# Tiny_Tetris_v1_0.net
KiCad netlist of a schematic drawn in EAGLE
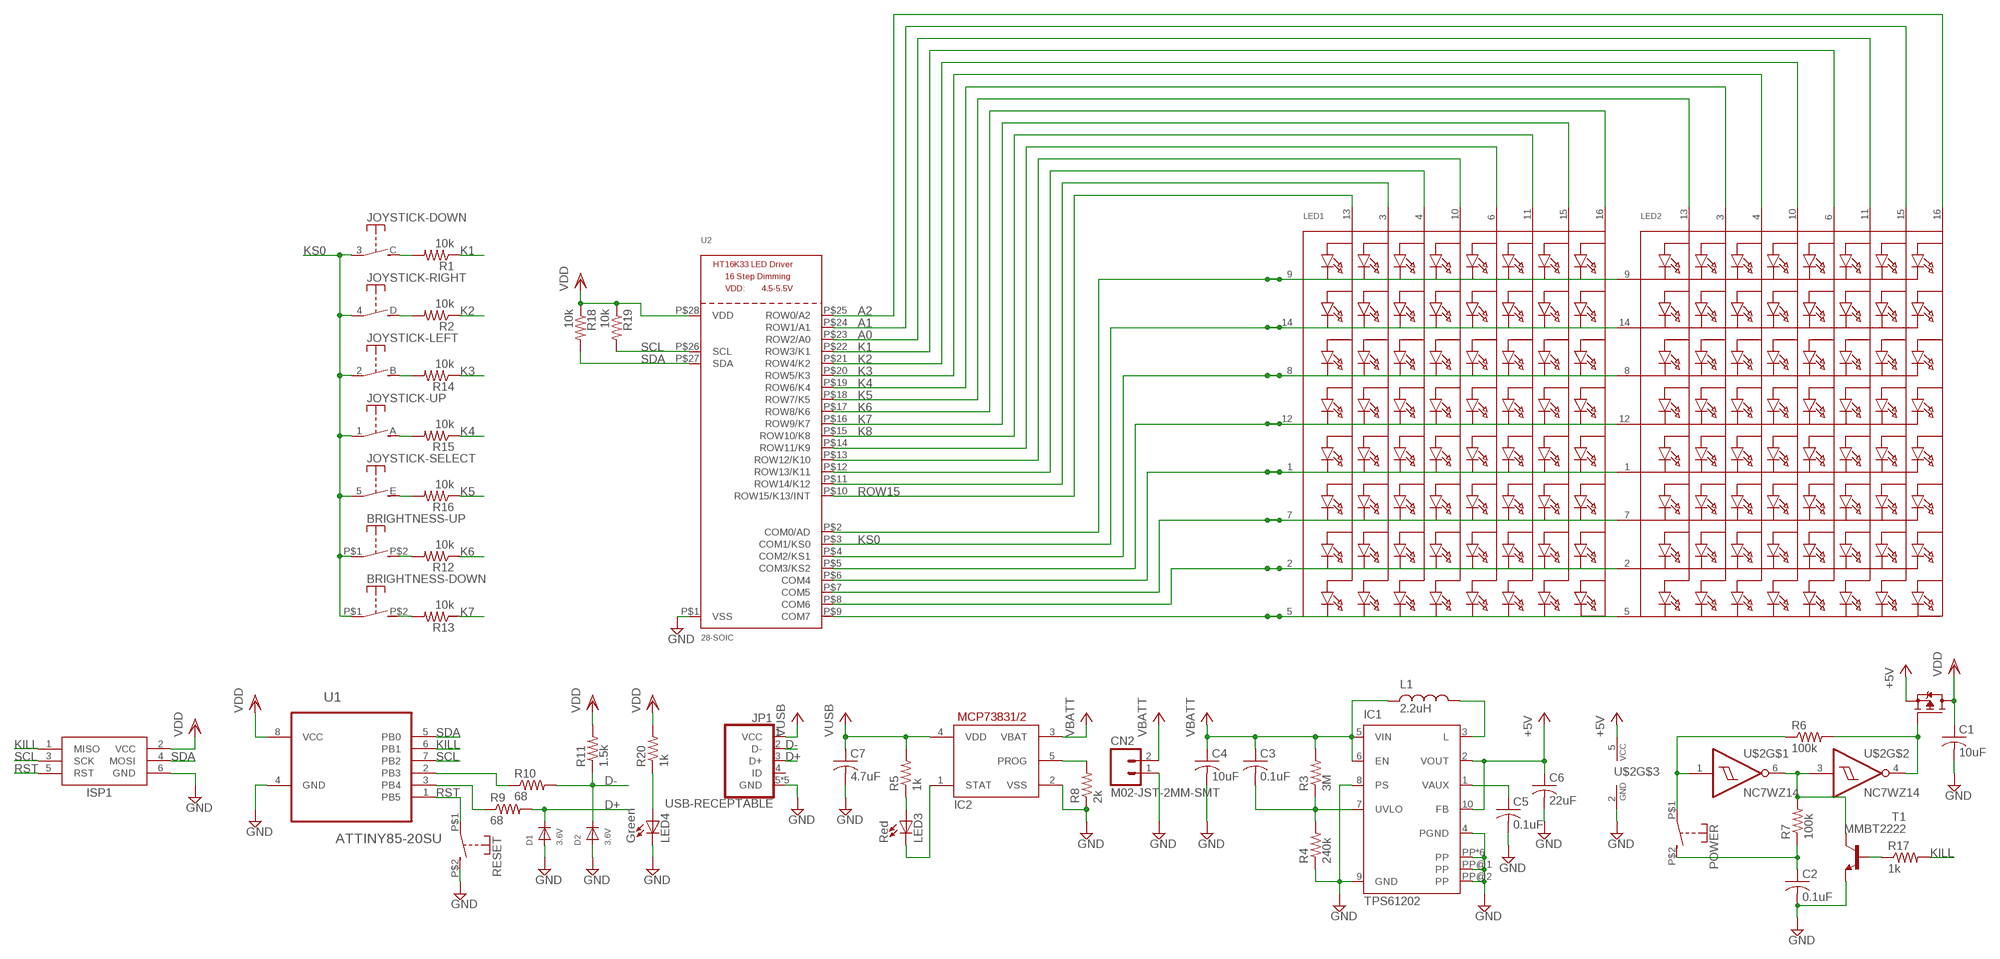
[diagram p0: schematic, sheet 1]

(export (version "E")
  (design (tool "Eeschema 10.0.6"))
  (components
    (comp (ref "BRIGHTNESS-DOWN")
      (value "SWITCH-TACTSKRELGE010")
      (footprint "eagle-import:TACT-ALPS-SKRELGE010")
      (libsource (lib "eagle-import") (part "SWITCH-TACTSKRELGE010"))
    )
    (comp (ref "BRIGHTNESS-UP")
      (value "SWITCH-TACTSKRELGE010")
      (footprint "eagle-import:TACT-ALPS-SKRELGE010")
      (libsource (lib "eagle-import") (part "SWITCH-TACTSKRELGE010"))
    )
    (comp (ref "C1")
      (value "10uF")
      (footprint "eagle-import:C0603K")
      (libsource (lib "eagle-import") (part "C-USC0603K"))
    )
    (comp (ref "C2")
      (value "0.1uF")
      (footprint "eagle-import:C0603K")
      (libsource (lib "eagle-import") (part "C-USC0603K"))
    )
    (comp (ref "C3")
      (value "0.1uF")
      (footprint "eagle-import:C0603K")
      (libsource (lib "eagle-import") (part "C-USC0603K"))
    )
    (comp (ref "C4")
      (value "10uF")
      (footprint "eagle-import:C0603K")
      (libsource (lib "eagle-import") (part "C-USC0603K"))
    )
    (comp (ref "C5")
      (value "0.1uF")
      (footprint "eagle-import:C0603K")
      (libsource (lib "eagle-import") (part "C-USC0603K"))
    )
    (comp (ref "C6")
      (value "22uF")
      (footprint "eagle-import:C0603K")
      (libsource (lib "eagle-import") (part "C-USC0603K"))
    )
    (comp (ref "C7")
      (value "4.7uF")
      (footprint "eagle-import:C0603K")
      (libsource (lib "eagle-import") (part "C-USC0603K"))
    )
    (comp (ref "CN2")
      (value "M02-JST-2MM-SMT")
      (footprint "eagle-import:1X02_NO_SILK")
      (libsource (lib "eagle-import") (part "M021X02_NO_SILK"))
    )
    (comp (ref "D1")
      (value "3.6V")
      (footprint "eagle-import:SOD-323")
      (libsource (lib "eagle-import") (part "DIODESOD-323"))
    )
    (comp (ref "D2")
      (value "3.6V")
      (footprint "eagle-import:SOD-323")
      (libsource (lib "eagle-import") (part "DIODESOD-323"))
    )
    (comp (ref "IC1")
      (value "TPS61202")
      (footprint "eagle-import:S-PDSO-N10")
      (fields (field (name "MPN") "TPS61202DRCR"))
      (libsource (lib "eagle-import") (part "TPS61202"))
    )
    (comp (ref "IC2")
      (value "MCP73831/OT")
      (footprint "eagle-import:SOT23-5L")
      (libsource (lib "eagle-import") (part "MCP73831/OT"))
    )
    (comp (ref "ISP1")
      (value "AVRISP-6")
      (footprint "eagle-import:AVRISP")
      (libsource (lib "eagle-import") (part "AVRISP-6"))
    )
    (comp (ref "JOYSTICK-")
      (value "SWITCH-NAVIGATION")
      (footprint "eagle-import:JOYSTICK-NOKIA-3230")
      (libsource (lib "eagle-import") (part "SWITCH-NAVIGATION"))
    )
    (comp (ref "JP1")
      (value "USB-RECEPTABLE")
      (footprint "eagle-import:FCI-10103594-0001LF")
      (libsource (lib "eagle-import") (part "USB-RECEPTABLE"))
    )
    (comp (ref "L1")
      (value "2.2uH")
      (footprint "eagle-import:LPS3015")
      (libsource (lib "eagle-import") (part "LPS3015"))
    )
    (comp (ref "LED1")
      (value "DISP_SEGMENT_8X8_ROWCATHODEBL-M12A883")
      (footprint "eagle-import:SEGMENT_BL-M12A883")
      (libsource (lib "eagle-import") (part "DISP_SEGMENT_8X8_ROWCATHODEBL-M12A883"))
    )
    (comp (ref "LED2")
      (value "DISP_SEGMENT_8X8_ROWCATHODEBL-M12A883")
      (footprint "eagle-import:SEGMENT_BL-M12A883")
      (libsource (lib "eagle-import") (part "DISP_SEGMENT_8X8_ROWCATHODEBL-M12A883"))
    )
    (comp (ref "LED3")
      (value "Red")
      (footprint "eagle-import:LED-0603-SIDEVIEW")
      (libsource (lib "eagle-import") (part "LED"))
    )
    (comp (ref "LED4")
      (value "Green")
      (footprint "eagle-import:LED-0603-SIDEVIEW")
      (libsource (lib "eagle-import") (part "LED"))
    )
    (comp (ref "POWER")
      (value "SWITCH-TACTSKRELGE010")
      (footprint "eagle-import:TACT-ALPS-SKRELGE010")
      (libsource (lib "eagle-import") (part "SWITCH-TACTSKRELGE010"))
    )
    (comp (ref "R1")
      (value "10k")
      (footprint "eagle-import:R0603")
      (libsource (lib "eagle-import") (part "R-US_R0603"))
    )
    (comp (ref "R2")
      (value "10k")
      (footprint "eagle-import:R0603")
      (libsource (lib "eagle-import") (part "R-US_R0603"))
    )
    (comp (ref "R3")
      (value "3M")
      (footprint "eagle-import:R0603")
      (libsource (lib "eagle-import") (part "R-US_R0603"))
    )
    (comp (ref "R4")
      (value "240k")
      (footprint "eagle-import:R0603")
      (libsource (lib "eagle-import") (part "R-US_R0603"))
    )
    (comp (ref "R5")
      (value "1k")
      (footprint "eagle-import:R0603")
      (libsource (lib "eagle-import") (part "R-US_R0603"))
    )
    (comp (ref "R6")
      (value "100k")
      (footprint "eagle-import:R0603")
      (libsource (lib "eagle-import") (part "R-US_R0603"))
    )
    (comp (ref "R7")
      (value "100k")
      (footprint "eagle-import:R0603")
      (libsource (lib "eagle-import") (part "R-US_R0603"))
    )
    (comp (ref "R8")
      (value "2k")
      (footprint "eagle-import:R0603")
      (libsource (lib "eagle-import") (part "R-US_R0603"))
    )
    (comp (ref "R9")
      (value "68")
      (footprint "eagle-import:R0603")
      (libsource (lib "eagle-import") (part "R-US_R0603"))
    )
    (comp (ref "R10")
      (value "68")
      (footprint "eagle-import:R0603")
      (libsource (lib "eagle-import") (part "R-US_R0603"))
    )
    (comp (ref "R11")
      (value "1.5k")
      (footprint "eagle-import:R0603")
      (libsource (lib "eagle-import") (part "R-US_R0603"))
    )
    (comp (ref "R12")
      (value "10k")
      (footprint "eagle-import:R0603")
      (libsource (lib "eagle-import") (part "R-US_R0603"))
    )
    (comp (ref "R13")
      (value "10k")
      (footprint "eagle-import:R0603")
      (libsource (lib "eagle-import") (part "R-US_R0603"))
    )
    (comp (ref "R14")
      (value "10k")
      (footprint "eagle-import:R0603")
      (libsource (lib "eagle-import") (part "R-US_R0603"))
    )
    (comp (ref "R15")
      (value "10k")
      (footprint "eagle-import:R0603")
      (libsource (lib "eagle-import") (part "R-US_R0603"))
    )
    (comp (ref "R16")
      (value "10k")
      (footprint "eagle-import:R0603")
      (libsource (lib "eagle-import") (part "R-US_R0603"))
    )
    (comp (ref "R17")
      (value "1k")
      (footprint "eagle-import:R0603")
      (libsource (lib "eagle-import") (part "R-US_R0603"))
    )
    (comp (ref "R18")
      (value "10k")
      (footprint "eagle-import:R0603")
      (libsource (lib "eagle-import") (part "R-US_R0603"))
    )
    (comp (ref "R19")
      (value "10k")
      (footprint "eagle-import:R0603")
      (libsource (lib "eagle-import") (part "R-US_R0603"))
    )
    (comp (ref "R20")
      (value "1k")
      (footprint "eagle-import:R0603")
      (libsource (lib "eagle-import") (part "R-US_R0603"))
    )
    (comp (ref "RESET")
      (value "SWITCH-TACTSKRELGE010")
      (footprint "eagle-import:TACT-ALPS-SKRELGE010")
      (libsource (lib "eagle-import") (part "SWITCH-TACTSKRELGE010"))
    )
    (comp (ref "T1")
      (value "MMBT2222")
      (footprint "eagle-import:SOT23-BEC")
      (libsource (lib "eagle-import") (part "-NPN-SOT23-BECMMBT2222ALT1"))
    )
    (comp (ref "U$1")
      (value "IRLML6402")
      (footprint "eagle-import:SOT23")
      (libsource (lib "eagle-import") (part "IRLML6402"))
    )
    (comp (ref "U$2")
      (value "NC7WZ14")
      (footprint "eagle-import:SC-70-6")
      (libsource (lib "eagle-import") (part "NC7WZ14"))
    )
    (comp (ref "U1")
      (value "ATTINY85-20SU")
      (footprint "eagle-import:SOIC127P798X216-8N")
      (libsource (lib "eagle-import") (part "ATTINY85-20SU"))
    )
    (comp (ref "U2")
      (value "28-SOIC")
      (footprint "eagle-import:SOP28_300MIL")
      (libsource (lib "eagle-import") (part "HT16K33_SOP28"))
    )
  )
  (nets
    (net (code "1") (name "+5V") (class "Default")
      (node (ref "C6") (pin "1") (pinfunction "1_1") (pintype "passive"))
      (node (ref "IC1") (pin "10") (pinfunction "FB_10") (pintype "input"))
      (node (ref "IC1") (pin "2") (pinfunction "VOUT_2") (pintype "passive"))
      (node (ref "U$1") (pin "2") (pinfunction "S_2") (pintype "passive"))
      (node (ref "U$2") (pin "5") (pinfunction "VCC_5") (pintype "power_in"))
    )
    (net (code "2") (name "/A0") (class "Default")
      (node (ref "LED2") (pin "11") (pinfunction "A6_11") (pintype "bidirectional"))
      (node (ref "U2") (pin "P$23") (pinfunction "ROW2/A0_P$23") (pintype "bidirectional"))
    )
    (net (code "3") (name "/A1") (class "Default")
      (node (ref "LED2") (pin "15") (pinfunction "A7_15") (pintype "bidirectional"))
      (node (ref "U2") (pin "P$24") (pinfunction "ROW1/A1_P$24") (pintype "bidirectional"))
    )
    (net (code "4") (name "/A2") (class "Default")
      (node (ref "LED2") (pin "16") (pinfunction "A8_16") (pintype "bidirectional"))
      (node (ref "U2") (pin "P$25") (pinfunction "ROW0/A2_P$25") (pintype "bidirectional"))
    )
    (net (code "5") (name "/D+") (class "Default")
      (node (ref "D1") (pin "C") (pinfunction "C_C") (pintype "passive"))
      (node (ref "JP1") (pin "3") (pinfunction "D+_3") (pintype "bidirectional"))
      (node (ref "R9") (pin "2") (pinfunction "2_2") (pintype "passive"))
    )
    (net (code "6") (name "/D-") (class "Default")
      (node (ref "D2") (pin "C") (pinfunction "C_C") (pintype "passive"))
      (node (ref "JP1") (pin "2") (pinfunction "D-_2") (pintype "bidirectional"))
      (node (ref "R10") (pin "2") (pinfunction "2_2") (pintype "passive"))
      (node (ref "R11") (pin "1") (pinfunction "1_1") (pintype "passive"))
    )
    (net (code "7") (name "/K1") (class "Default")
      (node (ref "LED2") (pin "6") (pinfunction "A5_6") (pintype "bidirectional"))
      (node (ref "R1") (pin "1") (pinfunction "1_1") (pintype "passive"))
      (node (ref "U2") (pin "P$22") (pinfunction "ROW3/K1_P$22") (pintype "bidirectional"))
    )
    (net (code "8") (name "/K2") (class "Default")
      (node (ref "LED2") (pin "10") (pinfunction "A4_10") (pintype "bidirectional"))
      (node (ref "R2") (pin "1") (pinfunction "1_1") (pintype "passive"))
      (node (ref "U2") (pin "P$21") (pinfunction "ROW4/K2_P$21") (pintype "bidirectional"))
    )
    (net (code "9") (name "/K3") (class "Default")
      (node (ref "LED2") (pin "4") (pinfunction "A3_4") (pintype "bidirectional"))
      (node (ref "R14") (pin "1") (pinfunction "1_1") (pintype "passive"))
      (node (ref "U2") (pin "P$20") (pinfunction "ROW5/K3_P$20") (pintype "bidirectional"))
    )
    (net (code "10") (name "/K4") (class "Default")
      (node (ref "LED2") (pin "3") (pinfunction "A2_3") (pintype "bidirectional"))
      (node (ref "R15") (pin "1") (pinfunction "1_1") (pintype "passive"))
      (node (ref "U2") (pin "P$19") (pinfunction "ROW6/K4_P$19") (pintype "bidirectional"))
    )
    (net (code "11") (name "/K5") (class "Default")
      (node (ref "LED2") (pin "13") (pinfunction "A1_13") (pintype "bidirectional"))
      (node (ref "R16") (pin "1") (pinfunction "1_1") (pintype "passive"))
      (node (ref "U2") (pin "P$18") (pinfunction "ROW7/K5_P$18") (pintype "bidirectional"))
    )
    (net (code "12") (name "/K6") (class "Default")
      (node (ref "LED1") (pin "16") (pinfunction "A8_16") (pintype "bidirectional"))
      (node (ref "R12") (pin "1") (pinfunction "1_1") (pintype "passive"))
      (node (ref "U2") (pin "P$17") (pinfunction "ROW8/K6_P$17") (pintype "bidirectional"))
    )
    (net (code "13") (name "/K7") (class "Default")
      (node (ref "LED1") (pin "15") (pinfunction "A7_15") (pintype "bidirectional"))
      (node (ref "R13") (pin "1") (pinfunction "1_1") (pintype "passive"))
      (node (ref "U2") (pin "P$16") (pinfunction "ROW9/K7_P$16") (pintype "bidirectional"))
    )
    (net (code "14") (name "/K8") (class "Default")
      (node (ref "LED1") (pin "11") (pinfunction "A6_11") (pintype "bidirectional"))
      (node (ref "U2") (pin "P$15") (pinfunction "ROW10/K8_P$15") (pintype "bidirectional"))
    )
    (net (code "15") (name "/KILL") (class "Default")
      (node (ref "ISP1") (pin "1") (pinfunction "MISO_1") (pintype "input"))
      (node (ref "R17") (pin "2") (pinfunction "2_2") (pintype "passive"))
      (node (ref "U1") (pin "6") (pinfunction "PB1_6") (pintype "bidirectional"))
    )
    (net (code "16") (name "/KS0") (class "Default")
      (node (ref "BRIGHTNESS-DOWN") (pin "P$1") (pinfunction "P_P$1") (pintype "passive"))
      (node (ref "BRIGHTNESS-UP") (pin "P$1") (pinfunction "P_P$1") (pintype "passive"))
      (node (ref "JOYSTICK-") (pin "1") (pinfunction "P_1") (pintype "passive"))
      (node (ref "JOYSTICK-") (pin "2") (pinfunction "P_2") (pintype "passive"))
      (node (ref "JOYSTICK-") (pin "3") (pinfunction "P_3") (pintype "passive"))
      (node (ref "JOYSTICK-") (pin "4") (pinfunction "P_4") (pintype "passive"))
      (node (ref "JOYSTICK-") (pin "5") (pinfunction "P_5") (pintype "passive"))
      (node (ref "LED1") (pin "14") (pinfunction "K2_14") (pintype "bidirectional"))
      (node (ref "LED2") (pin "14") (pinfunction "K2_14") (pintype "bidirectional"))
      (node (ref "U2") (pin "P$3") (pinfunction "COM1/KS0_P$3") (pintype "bidirectional"))
    )
    (net (code "17") (name "/ROW15") (class "Default")
      (node (ref "LED1") (pin "13") (pinfunction "A1_13") (pintype "bidirectional"))
      (node (ref "U2") (pin "P$10") (pinfunction "ROW15/K13/INT_P$10") (pintype "bidirectional"))
    )
    (net (code "18") (name "/RST") (class "Default")
      (node (ref "ISP1") (pin "5") (pinfunction "RST_5") (pintype "output"))
      (node (ref "RESET") (pin "P$1") (pinfunction "P_P$1") (pintype "passive"))
      (node (ref "U1") (pin "1") (pinfunction "PB5_1") (pintype "bidirectional"))
    )
    (net (code "19") (name "/SCL") (class "Default")
      (node (ref "ISP1") (pin "3") (pinfunction "SCK_3") (pintype "output"))
      (node (ref "R19") (pin "2") (pinfunction "2_2") (pintype "passive"))
      (node (ref "U1") (pin "7") (pinfunction "PB2_7") (pintype "bidirectional"))
      (node (ref "U2") (pin "P$26") (pinfunction "SCL_P$26") (pintype "bidirectional"))
    )
    (net (code "20") (name "/SDA") (class "Default")
      (node (ref "ISP1") (pin "4") (pinfunction "MOSI_4") (pintype "output"))
      (node (ref "R18") (pin "2") (pinfunction "2_2") (pintype "passive"))
      (node (ref "U1") (pin "5") (pinfunction "PB0_5") (pintype "bidirectional"))
      (node (ref "U2") (pin "P$27") (pinfunction "SDA_P$27") (pintype "bidirectional"))
    )
    (net (code "21") (name "GND") (class "Default")
      (node (ref "C1") (pin "2") (pinfunction "2_2") (pintype "passive"))
      (node (ref "C2") (pin "2") (pinfunction "2_2") (pintype "passive"))
      (node (ref "C4") (pin "2") (pinfunction "2_2") (pintype "passive"))
      (node (ref "C5") (pin "2") (pinfunction "2_2") (pintype "passive"))
      (node (ref "C6") (pin "2") (pinfunction "2_2") (pintype "passive"))
      (node (ref "C7") (pin "2") (pinfunction "2_2") (pintype "passive"))
      (node (ref "CN2") (pin "1") (pinfunction "1_1") (pintype "passive"))
      (node (ref "D1") (pin "A") (pinfunction "A_A") (pintype "passive"))
      (node (ref "D2") (pin "A") (pinfunction "A_A") (pintype "passive"))
      (node (ref "IC1") (pin "4") (pinfunction "PGND_4") (pintype "power_in"))
      (node (ref "IC1") (pin "8") (pinfunction "PS_8") (pintype "input"))
      (node (ref "IC1") (pin "9") (pinfunction "GND_9") (pintype "power_in"))
      (node (ref "IC1") (pin "PP") (pinfunction "PP_PP") (pintype "power_in"))
      (node (ref "IC1") (pin "PP@1") (pinfunction "PP_PP@1") (pintype "power_in"))
      (node (ref "IC1") (pin "PP@2") (pinfunction "PP_PP@2") (pintype "power_in"))
      (node (ref "IC1") (pin "PP@3") (pinfunction "PP_PP@3") (pintype "power_in"))
      (node (ref "IC1") (pin "PP@4") (pinfunction "PP_PP@4") (pintype "power_in"))
      (node (ref "IC1") (pin "PP@5") (pinfunction "PP_PP@5") (pintype "power_in"))
      (node (ref "IC1") (pin "PP@6") (pinfunction "PP_PP@6") (pintype "power_in"))
      (node (ref "IC1") (pin "PP@7") (pinfunction "PP_PP@7") (pintype "power_in"))
      (node (ref "IC2") (pin "2") (pinfunction "VSS_2") (pintype "power_in"))
      (node (ref "ISP1") (pin "6") (pinfunction "GND_6") (pintype "power_in"))
      (node (ref "JP1") (pin "5") (pinfunction "GND_5") (pintype "bidirectional"))
      (node (ref "JP1") (pin "P$1") (pinfunction "GND_P$1") (pintype "bidirectional"))
      (node (ref "JP1") (pin "P$2") (pinfunction "GND_P$2") (pintype "bidirectional"))
      (node (ref "JP1") (pin "P$3") (pinfunction "GND_P$3") (pintype "bidirectional"))
      (node (ref "JP1") (pin "P$4") (pinfunction "GND_P$4") (pintype "bidirectional"))
      (node (ref "LED4") (pin "P$2") (pinfunction "C_P$2") (pintype "passive"))
      (node (ref "R4") (pin "1") (pinfunction "1_1") (pintype "passive"))
      (node (ref "R8") (pin "1") (pinfunction "1_1") (pintype "passive"))
      (node (ref "RESET") (pin "P$2") (pinfunction "S_P$2") (pintype "passive"))
      (node (ref "T1") (pin "E") (pinfunction "E_E") (pintype "passive"))
      (node (ref "U$2") (pin "2") (pinfunction "GND_2") (pintype "power_in"))
      (node (ref "U1") (pin "4") (pinfunction "GND_4") (pintype "passive"))
      (node (ref "U2") (pin "P$1") (pinfunction "VSS_P$1") (pintype "bidirectional"))
    )
    (net (code "22") (name "Net-(BRIGHTNESS-DOWN-S)") (class "Default")
      (node (ref "BRIGHTNESS-DOWN") (pin "P$2") (pinfunction "S_P$2") (pintype "passive"))
      (node (ref "R13") (pin "2") (pinfunction "2_2") (pintype "passive"))
    )
    (net (code "23") (name "Net-(BRIGHTNESS-UP-S)") (class "Default")
      (node (ref "BRIGHTNESS-UP") (pin "P$2") (pinfunction "S_P$2") (pintype "passive"))
      (node (ref "R12") (pin "2") (pinfunction "2_2") (pintype "passive"))
    )
    (net (code "24") (name "Net-(IC1-L)") (class "Default")
      (node (ref "IC1") (pin "3") (pinfunction "L_3") (pintype "input"))
      (node (ref "L1") (pin "P$2") (pinfunction "P$2_P$2") (pintype "bidirectional"))
    )
    (net (code "25") (name "Net-(IC1-UVLO)") (class "Default")
      (node (ref "C3") (pin "2") (pinfunction "2_2") (pintype "passive"))
      (node (ref "IC1") (pin "7") (pinfunction "UVLO_7") (pintype "input"))
      (node (ref "R3") (pin "1") (pinfunction "1_1") (pintype "passive"))
      (node (ref "R4") (pin "2") (pinfunction "2_2") (pintype "passive"))
    )
    (net (code "26") (name "Net-(IC1-VAUX)") (class "Default")
      (node (ref "C5") (pin "1") (pinfunction "1_1") (pintype "passive"))
      (node (ref "IC1") (pin "1") (pinfunction "VAUX_1") (pintype "bidirectional"))
    )
    (net (code "27") (name "Net-(IC2-PROG)") (class "Default")
      (node (ref "IC2") (pin "5") (pinfunction "PROG_5") (pintype "input"))
      (node (ref "R8") (pin "2") (pinfunction "2_2") (pintype "passive"))
    )
    (net (code "28") (name "Net-(IC2-STAT)") (class "Default")
      (node (ref "IC2") (pin "1") (pinfunction "STAT_1") (pintype "output"))
      (node (ref "LED3") (pin "P$2") (pinfunction "C_P$2") (pintype "passive"))
    )
    (net (code "29") (name "Net-(JOYSTICK-A-S)") (class "Default")
      (node (ref "JOYSTICK-") (pin "C") (pinfunction "S_C") (pintype "passive"))
      (node (ref "R1") (pin "2") (pinfunction "2_2") (pintype "passive"))
    )
    (net (code "30") (name "Net-(JOYSTICK-B-S)") (class "Default")
      (node (ref "JOYSTICK-") (pin "B") (pinfunction "S_B") (pintype "passive"))
      (node (ref "R14") (pin "2") (pinfunction "2_2") (pintype "passive"))
    )
    (net (code "31") (name "Net-(JOYSTICK-C-S)") (class "Default")
      (node (ref "JOYSTICK-") (pin "D") (pinfunction "S_D") (pintype "passive"))
      (node (ref "R2") (pin "2") (pinfunction "2_2") (pintype "passive"))
    )
    (net (code "32") (name "Net-(JOYSTICK-D-S)") (class "Default")
      (node (ref "JOYSTICK-") (pin "E") (pinfunction "S_E") (pintype "passive"))
      (node (ref "R16") (pin "2") (pinfunction "2_2") (pintype "passive"))
    )
    (net (code "33") (name "Net-(JOYSTICK-E-S)") (class "Default")
      (node (ref "JOYSTICK-") (pin "A") (pinfunction "S_A") (pintype "passive"))
      (node (ref "R15") (pin "2") (pinfunction "2_2") (pintype "passive"))
    )
    (net (code "34") (name "Net-(LED1-A2)") (class "Default")
      (node (ref "LED1") (pin "3") (pinfunction "A2_3") (pintype "bidirectional"))
      (node (ref "U2") (pin "P$11") (pinfunction "ROW14/K12_P$11") (pintype "bidirectional"))
    )
    (net (code "35") (name "Net-(LED1-A3)") (class "Default")
      (node (ref "LED1") (pin "4") (pinfunction "A3_4") (pintype "bidirectional"))
      (node (ref "U2") (pin "P$12") (pinfunction "ROW13/K11_P$12") (pintype "bidirectional"))
    )
    (net (code "36") (name "Net-(LED1-A4)") (class "Default")
      (node (ref "LED1") (pin "10") (pinfunction "A4_10") (pintype "bidirectional"))
      (node (ref "U2") (pin "P$13") (pinfunction "ROW12/K10_P$13") (pintype "bidirectional"))
    )
    (net (code "37") (name "Net-(LED1-A5)") (class "Default")
      (node (ref "LED1") (pin "6") (pinfunction "A5_6") (pintype "bidirectional"))
      (node (ref "U2") (pin "P$14") (pinfunction "ROW11/K9_P$14") (pintype "bidirectional"))
    )
    (net (code "38") (name "Net-(LED1-K1)") (class "Default")
      (node (ref "LED1") (pin "9") (pinfunction "K1_9") (pintype "bidirectional"))
      (node (ref "LED2") (pin "9") (pinfunction "K1_9") (pintype "bidirectional"))
      (node (ref "U2") (pin "P$2") (pinfunction "COM0/AD_P$2") (pintype "bidirectional"))
    )
    (net (code "39") (name "Net-(LED1-K3)") (class "Default")
      (node (ref "LED1") (pin "8") (pinfunction "K3_8") (pintype "bidirectional"))
      (node (ref "LED2") (pin "8") (pinfunction "K3_8") (pintype "bidirectional"))
      (node (ref "U2") (pin "P$4") (pinfunction "COM2/KS1_P$4") (pintype "bidirectional"))
    )
    (net (code "40") (name "Net-(LED1-K4)") (class "Default")
      (node (ref "LED1") (pin "12") (pinfunction "K4_12") (pintype "bidirectional"))
      (node (ref "LED2") (pin "12") (pinfunction "K4_12") (pintype "bidirectional"))
      (node (ref "U2") (pin "P$5") (pinfunction "COM3/KS2_P$5") (pintype "bidirectional"))
    )
    (net (code "41") (name "Net-(LED1-K5)") (class "Default")
      (node (ref "LED1") (pin "1") (pinfunction "K5_1") (pintype "bidirectional"))
      (node (ref "LED2") (pin "1") (pinfunction "K5_1") (pintype "bidirectional"))
      (node (ref "U2") (pin "P$6") (pinfunction "COM4_P$6") (pintype "bidirectional"))
    )
    (net (code "42") (name "Net-(LED1-K6)") (class "Default")
      (node (ref "LED1") (pin "7") (pinfunction "K6_7") (pintype "bidirectional"))
      (node (ref "LED2") (pin "7") (pinfunction "K6_7") (pintype "bidirectional"))
      (node (ref "U2") (pin "P$7") (pinfunction "COM5_P$7") (pintype "bidirectional"))
    )
    (net (code "43") (name "Net-(LED1-K7)") (class "Default")
      (node (ref "LED1") (pin "2") (pinfunction "K7_2") (pintype "bidirectional"))
      (node (ref "LED2") (pin "2") (pinfunction "K7_2") (pintype "bidirectional"))
      (node (ref "U2") (pin "P$8") (pinfunction "COM6_P$8") (pintype "bidirectional"))
    )
    (net (code "44") (name "Net-(LED1-K8)") (class "Default")
      (node (ref "LED1") (pin "5") (pinfunction "K8_5") (pintype "bidirectional"))
      (node (ref "LED2") (pin "5") (pinfunction "K8_5") (pintype "bidirectional"))
      (node (ref "U2") (pin "P$9") (pinfunction "COM7_P$9") (pintype "bidirectional"))
    )
    (net (code "45") (name "Net-(LED3-A)") (class "Default")
      (node (ref "LED3") (pin "P$1") (pinfunction "A_P$1") (pintype "passive"))
      (node (ref "R5") (pin "1") (pinfunction "1_1") (pintype "passive"))
    )
    (net (code "46") (name "Net-(LED4-A)") (class "Default")
      (node (ref "LED4") (pin "P$1") (pinfunction "A_P$1") (pintype "passive"))
      (node (ref "R20") (pin "1") (pinfunction "1_1") (pintype "passive"))
    )
    (net (code "47") (name "Net-(POWER-P)") (class "Default")
      (node (ref "POWER") (pin "P$1") (pinfunction "P_P$1") (pintype "passive"))
      (node (ref "R6") (pin "1") (pinfunction "1_1") (pintype "passive"))
      (node (ref "U$2") (pin "1") (pinfunction "I_1") (pintype "input"))
    )
    (net (code "48") (name "Net-(POWER-S)") (class "Default")
      (node (ref "C2") (pin "1") (pinfunction "1_1") (pintype "passive"))
      (node (ref "POWER") (pin "P$2") (pinfunction "S_P$2") (pintype "passive"))
      (node (ref "R7") (pin "1") (pinfunction "1_1") (pintype "passive"))
    )
    (net (code "49") (name "Net-(R17-Pad1)") (class "Default")
      (node (ref "R17") (pin "1") (pinfunction "1_1") (pintype "passive"))
      (node (ref "T1") (pin "B") (pinfunction "B_B") (pintype "passive"))
    )
    (net (code "50") (name "Net-(U$1-G)") (class "Default")
      (node (ref "R6") (pin "2") (pinfunction "2_2") (pintype "passive"))
      (node (ref "U$1") (pin "1") (pinfunction "G_1") (pintype "passive"))
      (node (ref "U$2") (pin "4") (pinfunction "O_4") (pintype "output"))
    )
    (net (code "51") (name "Net-(U$2A-O)") (class "Default")
      (node (ref "R7") (pin "2") (pinfunction "2_2") (pintype "passive"))
      (node (ref "T1") (pin "C") (pinfunction "C_C") (pintype "passive"))
      (node (ref "U$2") (pin "3") (pinfunction "I_3") (pintype "input"))
      (node (ref "U$2") (pin "6") (pinfunction "O_6") (pintype "output"))
    )
    (net (code "52") (name "Net-(U1-PB3)") (class "Default")
      (node (ref "R10") (pin "1") (pinfunction "1_1") (pintype "passive"))
      (node (ref "U1") (pin "2") (pinfunction "PB3_2") (pintype "bidirectional"))
    )
    (net (code "53") (name "Net-(U1-PB4)") (class "Default")
      (node (ref "R9") (pin "1") (pinfunction "1_1") (pintype "passive"))
      (node (ref "U1") (pin "3") (pinfunction "PB4_3") (pintype "bidirectional"))
    )
    (net (code "54") (name "VBATT") (class "Default")
      (node (ref "C3") (pin "1") (pinfunction "1_1") (pintype "passive"))
      (node (ref "C4") (pin "1") (pinfunction "1_1") (pintype "passive"))
      (node (ref "CN2") (pin "2") (pinfunction "2_2") (pintype "passive"))
      (node (ref "IC1") (pin "5") (pinfunction "VIN_5") (pintype "input"))
      (node (ref "IC1") (pin "6") (pinfunction "EN_6") (pintype "input"))
      (node (ref "IC2") (pin "3") (pinfunction "VBAT_3") (pintype "bidirectional"))
      (node (ref "L1") (pin "P$1") (pinfunction "P$1_P$1") (pintype "bidirectional"))
      (node (ref "R3") (pin "2") (pinfunction "2_2") (pintype "passive"))
    )
    (net (code "55") (name "VDD") (class "Default")
      (node (ref "C1") (pin "1") (pinfunction "1_1") (pintype "passive"))
      (node (ref "ISP1") (pin "2") (pinfunction "VCC_2") (pintype "power_in"))
      (node (ref "R11") (pin "2") (pinfunction "2_2") (pintype "passive"))
      (node (ref "R18") (pin "1") (pinfunction "1_1") (pintype "passive"))
      (node (ref "R19") (pin "1") (pinfunction "1_1") (pintype "passive"))
      (node (ref "R20") (pin "2") (pinfunction "2_2") (pintype "passive"))
      (node (ref "U$1") (pin "3") (pinfunction "D_3") (pintype "passive"))
      (node (ref "U1") (pin "8") (pinfunction "VCC_8") (pintype "power_in"))
      (node (ref "U2") (pin "P$28") (pinfunction "VDD_P$28") (pintype "bidirectional"))
    )
    (net (code "56") (name "VUSB") (class "Default")
      (node (ref "C7") (pin "1") (pinfunction "1_1") (pintype "passive"))
      (node (ref "IC2") (pin "4") (pinfunction "VDD_4") (pintype "power_in"))
      (node (ref "JP1") (pin "1") (pinfunction "VCC_1") (pintype "bidirectional"))
      (node (ref "R5") (pin "2") (pinfunction "2_2") (pintype "passive"))
    )
    (net (code "57") (name "unconnected-(JP1-ID-Pad4)") (class "Default")
      (node (ref "JP1") (pin "4") (pinfunction "ID_4") (pintype "bidirectional"))
    )
  )
)
